# LCs.net
KiCad netlist of a schematic drawn in Altium Designer
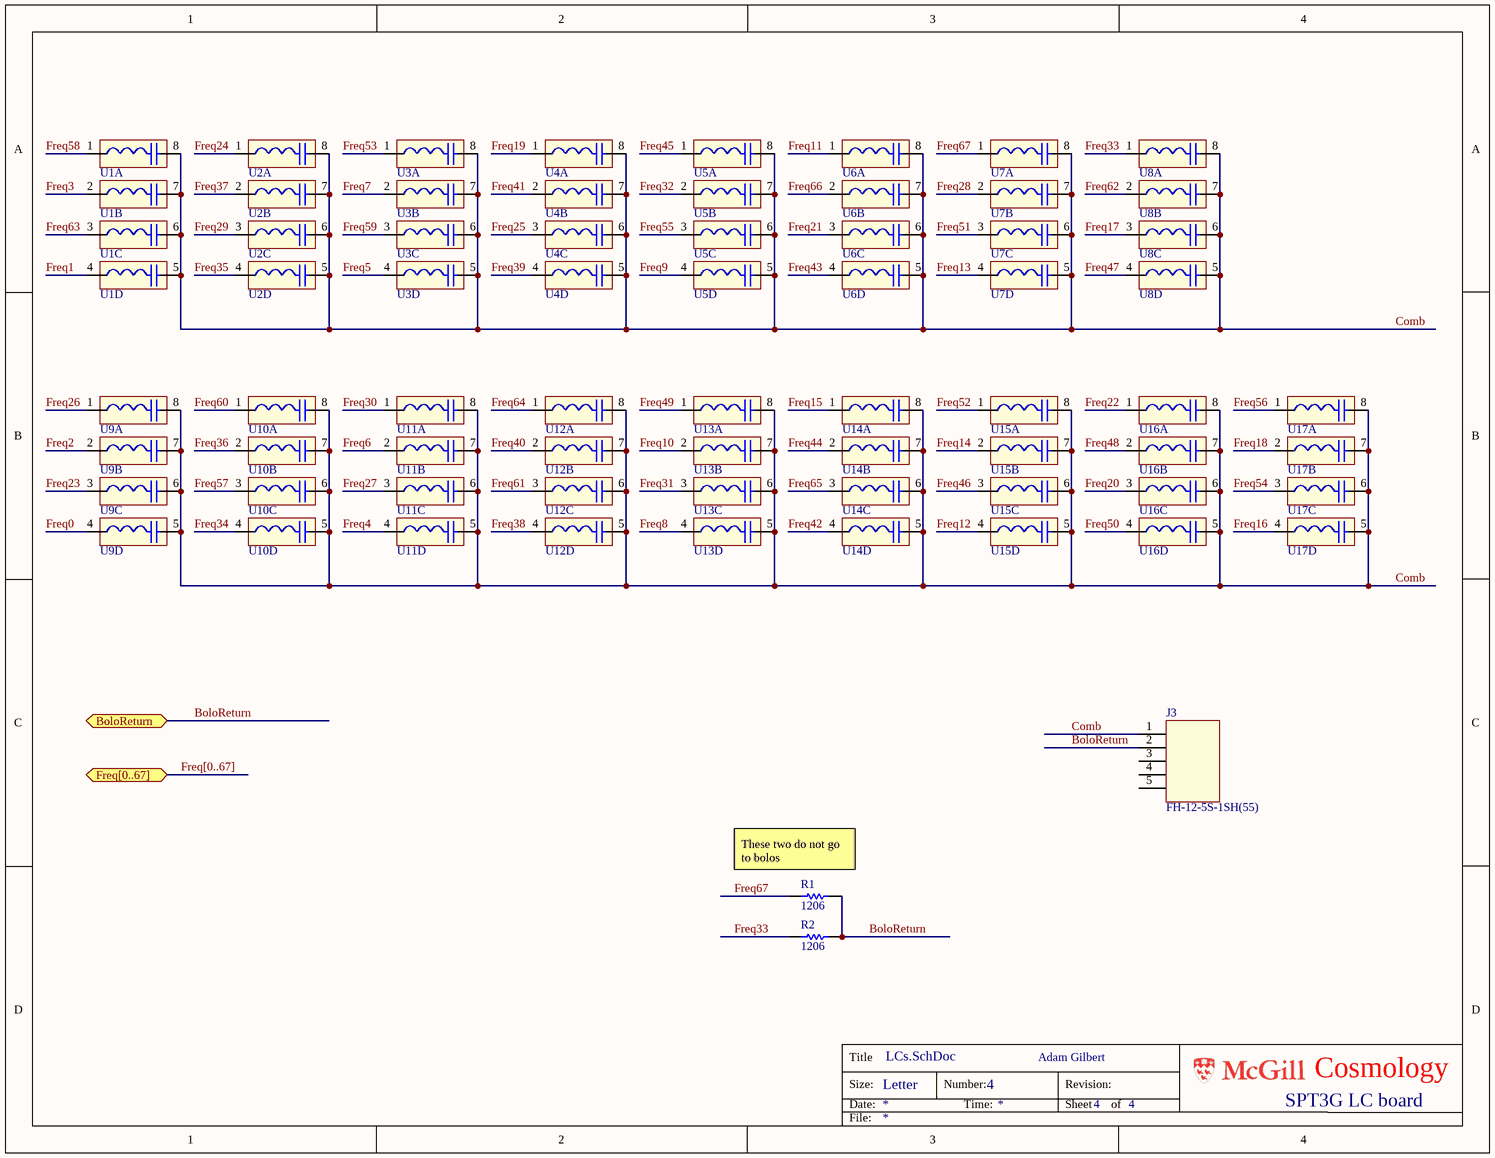
[diagram p0: LCs.SchDoc]

(export (version "E")
  (design (tool "Eeschema 10.0.6"))
  (components
    (comp (ref "J3")
      (value "FH-12-5S-1SH(55)")
      (footprint "FH-12-5S-1SH(55)")
      (libsource (lib "SPT3G_LCBoard") (part "FH-12-5S-1SH(55)"))
    )
    (comp (ref "R1")
      (value "Res1206")
      (footprint "1206")
      (description "Resistor")
      (libsource (lib "SPT3G_LCBoard") (part "Res1206"))
    )
    (comp (ref "R2")
      (value "Res1206")
      (footprint "1206")
      (description "Resistor")
      (libsource (lib "SPT3G_LCBoard") (part "Res1206"))
    )
    (comp (ref "U1")
      (value "LC_wafer")
      (footprint "LCCHIP4X2 - BondPads1")
      (description "Gold bonded integrated LC")
      (libsource (lib "SPT3G_LCBoard") (part "LCWafer"))
    )
    (comp (ref "U2")
      (value "LC_wafer")
      (footprint "LCCHIP4X2 - BondPads1")
      (description "Gold bonded integrated LC")
      (libsource (lib "SPT3G_LCBoard") (part "LCWafer"))
    )
    (comp (ref "U3")
      (value "LC_wafer")
      (footprint "LCCHIP4X2 - BondPads1")
      (description "Gold bonded integrated LC")
      (libsource (lib "SPT3G_LCBoard") (part "LCWafer"))
    )
    (comp (ref "U4")
      (value "LC_wafer")
      (footprint "LCCHIP4X2 - BondPads1")
      (description "Gold bonded integrated LC")
      (libsource (lib "SPT3G_LCBoard") (part "LCWafer"))
    )
    (comp (ref "U5")
      (value "LC_wafer")
      (footprint "LCCHIP4X2 - BondPads1")
      (description "Gold bonded integrated LC")
      (libsource (lib "SPT3G_LCBoard") (part "LCWafer"))
    )
    (comp (ref "U6")
      (value "LC_wafer")
      (footprint "LCCHIP4X2 - BondPads1")
      (description "Gold bonded integrated LC")
      (libsource (lib "SPT3G_LCBoard") (part "LCWafer"))
    )
    (comp (ref "U7")
      (value "LC_wafer")
      (footprint "LCCHIP4X2 - BondPads1")
      (description "Gold bonded integrated LC")
      (libsource (lib "SPT3G_LCBoard") (part "LCWafer"))
    )
    (comp (ref "U8")
      (value "LC_wafer")
      (footprint "LCCHIP4X2 - BondPads1")
      (description "Gold bonded integrated LC")
      (libsource (lib "SPT3G_LCBoard") (part "LCWafer"))
    )
    (comp (ref "U9")
      (value "LC_wafer")
      (footprint "LCCHIP4X2 - BondPads1")
      (description "Gold bonded integrated LC")
      (libsource (lib "SPT3G_LCBoard") (part "LCWafer"))
    )
    (comp (ref "U10")
      (value "LC_wafer")
      (footprint "LCCHIP4X2 - BondPads1")
      (description "Gold bonded integrated LC")
      (libsource (lib "SPT3G_LCBoard") (part "LCWafer"))
    )
    (comp (ref "U11")
      (value "LC_wafer")
      (footprint "LCCHIP4X2 - BondPads1")
      (description "Gold bonded integrated LC")
      (libsource (lib "SPT3G_LCBoard") (part "LCWafer"))
    )
    (comp (ref "U12")
      (value "LC_wafer")
      (footprint "LCCHIP4X2 - BondPads1")
      (description "Gold bonded integrated LC")
      (libsource (lib "SPT3G_LCBoard") (part "LCWafer"))
    )
    (comp (ref "U13")
      (value "LC_wafer")
      (footprint "LCCHIP4X2 - BondPads1")
      (description "Gold bonded integrated LC")
      (libsource (lib "SPT3G_LCBoard") (part "LCWafer"))
    )
    (comp (ref "U14")
      (value "LC_wafer")
      (footprint "LCCHIP4X2 - BondPads1")
      (description "Gold bonded integrated LC")
      (libsource (lib "SPT3G_LCBoard") (part "LCWafer"))
    )
    (comp (ref "U15")
      (value "LC_wafer")
      (footprint "LCCHIP4X2 - BondPads1")
      (description "Gold bonded integrated LC")
      (libsource (lib "SPT3G_LCBoard") (part "LCWafer"))
    )
    (comp (ref "U16")
      (value "LC_wafer")
      (footprint "LCCHIP4X2 - BondPads1")
      (description "Gold bonded integrated LC")
      (libsource (lib "SPT3G_LCBoard") (part "LCWafer"))
    )
    (comp (ref "U17")
      (value "LC_wafer")
      (footprint "LCCHIP4X2 - BondPads1")
      (description "Gold bonded integrated LC")
      (libsource (lib "SPT3G_LCBoard") (part "LCWafer"))
    )
  )
  (nets
    (net (code "1") (name "/BoloReturn") (class "Default")
      (node (ref "J3") (pin "2") (pinfunction "2_2") (pintype "passive"))
      (node (ref "R1") (pin "2") (pinfunction "2_2") (pintype "passive"))
      (node (ref "R2") (pin "2") (pinfunction "2_2") (pintype "passive"))
    )
    (net (code "2") (name "/Comb") (class "Default")
      (node (ref "J3") (pin "1") (pinfunction "1_1") (pintype "passive"))
      (node (ref "U1") (pin "5") (pinfunction "5_5") (pintype "passive"))
      (node (ref "U1") (pin "6") (pinfunction "6_6") (pintype "passive"))
      (node (ref "U1") (pin "7") (pinfunction "7_7") (pintype "passive"))
      (node (ref "U1") (pin "8") (pinfunction "8_8") (pintype "passive"))
      (node (ref "U10") (pin "5") (pinfunction "5_5") (pintype "passive"))
      (node (ref "U10") (pin "6") (pinfunction "6_6") (pintype "passive"))
      (node (ref "U10") (pin "7") (pinfunction "7_7") (pintype "passive"))
      (node (ref "U10") (pin "8") (pinfunction "8_8") (pintype "passive"))
      (node (ref "U11") (pin "5") (pinfunction "5_5") (pintype "passive"))
      (node (ref "U11") (pin "6") (pinfunction "6_6") (pintype "passive"))
      (node (ref "U11") (pin "7") (pinfunction "7_7") (pintype "passive"))
      (node (ref "U11") (pin "8") (pinfunction "8_8") (pintype "passive"))
      (node (ref "U12") (pin "5") (pinfunction "5_5") (pintype "passive"))
      (node (ref "U12") (pin "6") (pinfunction "6_6") (pintype "passive"))
      (node (ref "U12") (pin "7") (pinfunction "7_7") (pintype "passive"))
      (node (ref "U12") (pin "8") (pinfunction "8_8") (pintype "passive"))
      (node (ref "U13") (pin "5") (pinfunction "5_5") (pintype "passive"))
      (node (ref "U13") (pin "6") (pinfunction "6_6") (pintype "passive"))
      (node (ref "U13") (pin "7") (pinfunction "7_7") (pintype "passive"))
      (node (ref "U13") (pin "8") (pinfunction "8_8") (pintype "passive"))
      (node (ref "U14") (pin "5") (pinfunction "5_5") (pintype "passive"))
      (node (ref "U14") (pin "6") (pinfunction "6_6") (pintype "passive"))
      (node (ref "U14") (pin "7") (pinfunction "7_7") (pintype "passive"))
      (node (ref "U14") (pin "8") (pinfunction "8_8") (pintype "passive"))
      (node (ref "U15") (pin "5") (pinfunction "5_5") (pintype "passive"))
      (node (ref "U15") (pin "6") (pinfunction "6_6") (pintype "passive"))
      (node (ref "U15") (pin "7") (pinfunction "7_7") (pintype "passive"))
      (node (ref "U15") (pin "8") (pinfunction "8_8") (pintype "passive"))
      (node (ref "U16") (pin "5") (pinfunction "5_5") (pintype "passive"))
      (node (ref "U16") (pin "6") (pinfunction "6_6") (pintype "passive"))
      (node (ref "U16") (pin "7") (pinfunction "7_7") (pintype "passive"))
      (node (ref "U16") (pin "8") (pinfunction "8_8") (pintype "passive"))
      (node (ref "U17") (pin "5") (pinfunction "5_5") (pintype "passive"))
      (node (ref "U17") (pin "6") (pinfunction "6_6") (pintype "passive"))
      (node (ref "U17") (pin "7") (pinfunction "7_7") (pintype "passive"))
      (node (ref "U17") (pin "8") (pinfunction "8_8") (pintype "passive"))
      (node (ref "U2") (pin "5") (pinfunction "5_5") (pintype "passive"))
      (node (ref "U2") (pin "6") (pinfunction "6_6") (pintype "passive"))
      (node (ref "U2") (pin "7") (pinfunction "7_7") (pintype "passive"))
      (node (ref "U2") (pin "8") (pinfunction "8_8") (pintype "passive"))
      (node (ref "U3") (pin "5") (pinfunction "5_5") (pintype "passive"))
      (node (ref "U3") (pin "6") (pinfunction "6_6") (pintype "passive"))
      (node (ref "U3") (pin "7") (pinfunction "7_7") (pintype "passive"))
      (node (ref "U3") (pin "8") (pinfunction "8_8") (pintype "passive"))
      (node (ref "U4") (pin "5") (pinfunction "5_5") (pintype "passive"))
      (node (ref "U4") (pin "6") (pinfunction "6_6") (pintype "passive"))
      (node (ref "U4") (pin "7") (pinfunction "7_7") (pintype "passive"))
      (node (ref "U4") (pin "8") (pinfunction "8_8") (pintype "passive"))
      (node (ref "U5") (pin "5") (pinfunction "5_5") (pintype "passive"))
      (node (ref "U5") (pin "6") (pinfunction "6_6") (pintype "passive"))
      (node (ref "U5") (pin "7") (pinfunction "7_7") (pintype "passive"))
      (node (ref "U5") (pin "8") (pinfunction "8_8") (pintype "passive"))
      (node (ref "U6") (pin "5") (pinfunction "5_5") (pintype "passive"))
      (node (ref "U6") (pin "6") (pinfunction "6_6") (pintype "passive"))
      (node (ref "U6") (pin "7") (pinfunction "7_7") (pintype "passive"))
      (node (ref "U6") (pin "8") (pinfunction "8_8") (pintype "passive"))
      (node (ref "U7") (pin "5") (pinfunction "5_5") (pintype "passive"))
      (node (ref "U7") (pin "6") (pinfunction "6_6") (pintype "passive"))
      (node (ref "U7") (pin "7") (pinfunction "7_7") (pintype "passive"))
      (node (ref "U7") (pin "8") (pinfunction "8_8") (pintype "passive"))
      (node (ref "U8") (pin "5") (pinfunction "5_5") (pintype "passive"))
      (node (ref "U8") (pin "6") (pinfunction "6_6") (pintype "passive"))
      (node (ref "U8") (pin "7") (pinfunction "7_7") (pintype "passive"))
      (node (ref "U8") (pin "8") (pinfunction "8_8") (pintype "passive"))
      (node (ref "U9") (pin "5") (pinfunction "5_5") (pintype "passive"))
      (node (ref "U9") (pin "6") (pinfunction "6_6") (pintype "passive"))
      (node (ref "U9") (pin "7") (pinfunction "7_7") (pintype "passive"))
      (node (ref "U9") (pin "8") (pinfunction "8_8") (pintype "passive"))
    )
    (net (code "3") (name "/Freq0") (class "Default")
      (node (ref "U9") (pin "4") (pinfunction "4_4") (pintype "passive"))
    )
    (net (code "4") (name "/Freq1") (class "Default")
      (node (ref "U1") (pin "4") (pinfunction "4_4") (pintype "passive"))
    )
    (net (code "5") (name "/Freq2") (class "Default")
      (node (ref "U9") (pin "2") (pinfunction "2_2") (pintype "passive"))
    )
    (net (code "6") (name "/Freq3") (class "Default")
      (node (ref "U1") (pin "2") (pinfunction "2_2") (pintype "passive"))
    )
    (net (code "7") (name "/Freq4") (class "Default")
      (node (ref "U11") (pin "4") (pinfunction "4_4") (pintype "passive"))
    )
    (net (code "8") (name "/Freq5") (class "Default")
      (node (ref "U3") (pin "4") (pinfunction "4_4") (pintype "passive"))
    )
    (net (code "9") (name "/Freq6") (class "Default")
      (node (ref "U11") (pin "2") (pinfunction "2_2") (pintype "passive"))
    )
    (net (code "10") (name "/Freq7") (class "Default")
      (node (ref "U3") (pin "2") (pinfunction "2_2") (pintype "passive"))
    )
    (net (code "11") (name "/Freq8") (class "Default")
      (node (ref "U13") (pin "4") (pinfunction "4_4") (pintype "passive"))
    )
    (net (code "12") (name "/Freq9") (class "Default")
      (node (ref "U5") (pin "4") (pinfunction "4_4") (pintype "passive"))
    )
    (net (code "13") (name "/Freq10") (class "Default")
      (node (ref "U13") (pin "2") (pinfunction "2_2") (pintype "passive"))
    )
    (net (code "14") (name "/Freq11") (class "Default")
      (node (ref "U6") (pin "1") (pinfunction "1_1") (pintype "passive"))
    )
    (net (code "15") (name "/Freq12") (class "Default")
      (node (ref "U15") (pin "4") (pinfunction "4_4") (pintype "passive"))
    )
    (net (code "16") (name "/Freq13") (class "Default")
      (node (ref "U7") (pin "4") (pinfunction "4_4") (pintype "passive"))
    )
    (net (code "17") (name "/Freq14") (class "Default")
      (node (ref "U15") (pin "2") (pinfunction "2_2") (pintype "passive"))
    )
    (net (code "18") (name "/Freq15") (class "Default")
      (node (ref "U14") (pin "1") (pinfunction "1_1") (pintype "passive"))
    )
    (net (code "19") (name "/Freq16") (class "Default")
      (node (ref "U17") (pin "4") (pinfunction "4_4") (pintype "passive"))
    )
    (net (code "20") (name "/Freq17") (class "Default")
      (node (ref "U8") (pin "3") (pinfunction "3_3") (pintype "passive"))
    )
    (net (code "21") (name "/Freq18") (class "Default")
      (node (ref "U17") (pin "2") (pinfunction "2_2") (pintype "passive"))
    )
    (net (code "22") (name "/Freq19") (class "Default")
      (node (ref "U4") (pin "1") (pinfunction "1_1") (pintype "passive"))
    )
    (net (code "23") (name "/Freq20") (class "Default")
      (node (ref "U16") (pin "3") (pinfunction "3_3") (pintype "passive"))
    )
    (net (code "24") (name "/Freq21") (class "Default")
      (node (ref "U6") (pin "3") (pinfunction "3_3") (pintype "passive"))
    )
    (net (code "25") (name "/Freq22") (class "Default")
      (node (ref "U16") (pin "1") (pinfunction "1_1") (pintype "passive"))
    )
    (net (code "26") (name "/Freq23") (class "Default")
      (node (ref "U9") (pin "3") (pinfunction "3_3") (pintype "passive"))
    )
    (net (code "27") (name "/Freq24") (class "Default")
      (node (ref "U2") (pin "1") (pinfunction "1_1") (pintype "passive"))
    )
    (net (code "28") (name "/Freq25") (class "Default")
      (node (ref "U4") (pin "3") (pinfunction "3_3") (pintype "passive"))
    )
    (net (code "29") (name "/Freq26") (class "Default")
      (node (ref "U9") (pin "1") (pinfunction "1_1") (pintype "passive"))
    )
    (net (code "30") (name "/Freq27") (class "Default")
      (node (ref "U11") (pin "3") (pinfunction "3_3") (pintype "passive"))
    )
    (net (code "31") (name "/Freq28") (class "Default")
      (node (ref "U7") (pin "2") (pinfunction "2_2") (pintype "passive"))
    )
    (net (code "32") (name "/Freq29") (class "Default")
      (node (ref "U2") (pin "3") (pinfunction "3_3") (pintype "passive"))
    )
    (net (code "33") (name "/Freq30") (class "Default")
      (node (ref "U11") (pin "1") (pinfunction "1_1") (pintype "passive"))
    )
    (net (code "34") (name "/Freq31") (class "Default")
      (node (ref "U13") (pin "3") (pinfunction "3_3") (pintype "passive"))
    )
    (net (code "35") (name "/Freq32") (class "Default")
      (node (ref "U5") (pin "2") (pinfunction "2_2") (pintype "passive"))
    )
    (net (code "36") (name "/Freq33") (class "Default")
      (node (ref "R2") (pin "1") (pinfunction "1_1") (pintype "passive"))
      (node (ref "U8") (pin "1") (pinfunction "1_1") (pintype "passive"))
    )
    (net (code "37") (name "/Freq34") (class "Default")
      (node (ref "U10") (pin "4") (pinfunction "4_4") (pintype "passive"))
    )
    (net (code "38") (name "/Freq35") (class "Default")
      (node (ref "U2") (pin "4") (pinfunction "4_4") (pintype "passive"))
    )
    (net (code "39") (name "/Freq36") (class "Default")
      (node (ref "U10") (pin "2") (pinfunction "2_2") (pintype "passive"))
    )
    (net (code "40") (name "/Freq37") (class "Default")
      (node (ref "U2") (pin "2") (pinfunction "2_2") (pintype "passive"))
    )
    (net (code "41") (name "/Freq38") (class "Default")
      (node (ref "U12") (pin "4") (pinfunction "4_4") (pintype "passive"))
    )
    (net (code "42") (name "/Freq39") (class "Default")
      (node (ref "U4") (pin "4") (pinfunction "4_4") (pintype "passive"))
    )
    (net (code "43") (name "/Freq40") (class "Default")
      (node (ref "U12") (pin "2") (pinfunction "2_2") (pintype "passive"))
    )
    (net (code "44") (name "/Freq41") (class "Default")
      (node (ref "U4") (pin "2") (pinfunction "2_2") (pintype "passive"))
    )
    (net (code "45") (name "/Freq42") (class "Default")
      (node (ref "U14") (pin "4") (pinfunction "4_4") (pintype "passive"))
    )
    (net (code "46") (name "/Freq43") (class "Default")
      (node (ref "U6") (pin "4") (pinfunction "4_4") (pintype "passive"))
    )
    (net (code "47") (name "/Freq44") (class "Default")
      (node (ref "U14") (pin "2") (pinfunction "2_2") (pintype "passive"))
    )
    (net (code "48") (name "/Freq45") (class "Default")
      (node (ref "U5") (pin "1") (pinfunction "1_1") (pintype "passive"))
    )
    (net (code "49") (name "/Freq46") (class "Default")
      (node (ref "U15") (pin "3") (pinfunction "3_3") (pintype "passive"))
    )
    (net (code "50") (name "/Freq47") (class "Default")
      (node (ref "U8") (pin "4") (pinfunction "4_4") (pintype "passive"))
    )
    (net (code "51") (name "/Freq48") (class "Default")
      (node (ref "U16") (pin "2") (pinfunction "2_2") (pintype "passive"))
    )
    (net (code "52") (name "/Freq49") (class "Default")
      (node (ref "U13") (pin "1") (pinfunction "1_1") (pintype "passive"))
    )
    (net (code "53") (name "/Freq50") (class "Default")
      (node (ref "U16") (pin "4") (pinfunction "4_4") (pintype "passive"))
    )
    (net (code "54") (name "/Freq51") (class "Default")
      (node (ref "U7") (pin "3") (pinfunction "3_3") (pintype "passive"))
    )
    (net (code "55") (name "/Freq52") (class "Default")
      (node (ref "U15") (pin "1") (pinfunction "1_1") (pintype "passive"))
    )
    (net (code "56") (name "/Freq53") (class "Default")
      (node (ref "U3") (pin "1") (pinfunction "1_1") (pintype "passive"))
    )
    (net (code "57") (name "/Freq54") (class "Default")
      (node (ref "U17") (pin "3") (pinfunction "3_3") (pintype "passive"))
    )
    (net (code "58") (name "/Freq55") (class "Default")
      (node (ref "U5") (pin "3") (pinfunction "3_3") (pintype "passive"))
    )
    (net (code "59") (name "/Freq56") (class "Default")
      (node (ref "U17") (pin "1") (pinfunction "1_1") (pintype "passive"))
    )
    (net (code "60") (name "/Freq57") (class "Default")
      (node (ref "U10") (pin "3") (pinfunction "3_3") (pintype "passive"))
    )
    (net (code "61") (name "/Freq58") (class "Default")
      (node (ref "U1") (pin "1") (pinfunction "1_1") (pintype "passive"))
    )
    (net (code "62") (name "/Freq59") (class "Default")
      (node (ref "U3") (pin "3") (pinfunction "3_3") (pintype "passive"))
    )
    (net (code "63") (name "/Freq60") (class "Default")
      (node (ref "U10") (pin "1") (pinfunction "1_1") (pintype "passive"))
    )
    (net (code "64") (name "/Freq61") (class "Default")
      (node (ref "U12") (pin "3") (pinfunction "3_3") (pintype "passive"))
    )
    (net (code "65") (name "/Freq62") (class "Default")
      (node (ref "U8") (pin "2") (pinfunction "2_2") (pintype "passive"))
    )
    (net (code "66") (name "/Freq63") (class "Default")
      (node (ref "U1") (pin "3") (pinfunction "3_3") (pintype "passive"))
    )
    (net (code "67") (name "/Freq64") (class "Default")
      (node (ref "U12") (pin "1") (pinfunction "1_1") (pintype "passive"))
    )
    (net (code "68") (name "/Freq65") (class "Default")
      (node (ref "U14") (pin "3") (pinfunction "3_3") (pintype "passive"))
    )
    (net (code "69") (name "/Freq66") (class "Default")
      (node (ref "U6") (pin "2") (pinfunction "2_2") (pintype "passive"))
    )
    (net (code "70") (name "/Freq67") (class "Default")
      (node (ref "R1") (pin "1") (pinfunction "1_1") (pintype "passive"))
      (node (ref "U7") (pin "1") (pinfunction "1_1") (pintype "passive"))
    )
    (net (code "72") (name "unconnected-(J3-Pad3)") (class "Default")
      (node (ref "J3") (pin "3") (pinfunction "3_3") (pintype "passive"))
    )
    (net (code "73") (name "unconnected-(J3-Pad4)") (class "Default")
      (node (ref "J3") (pin "4") (pinfunction "4_4") (pintype "passive"))
    )
    (net (code "74") (name "unconnected-(J3-Pad5)") (class "Default")
      (node (ref "J3") (pin "5") (pinfunction "5_5") (pintype "passive"))
    )
  )
)
